# audio_router.net
KiCad netlist of a schematic drawn in EAGLE
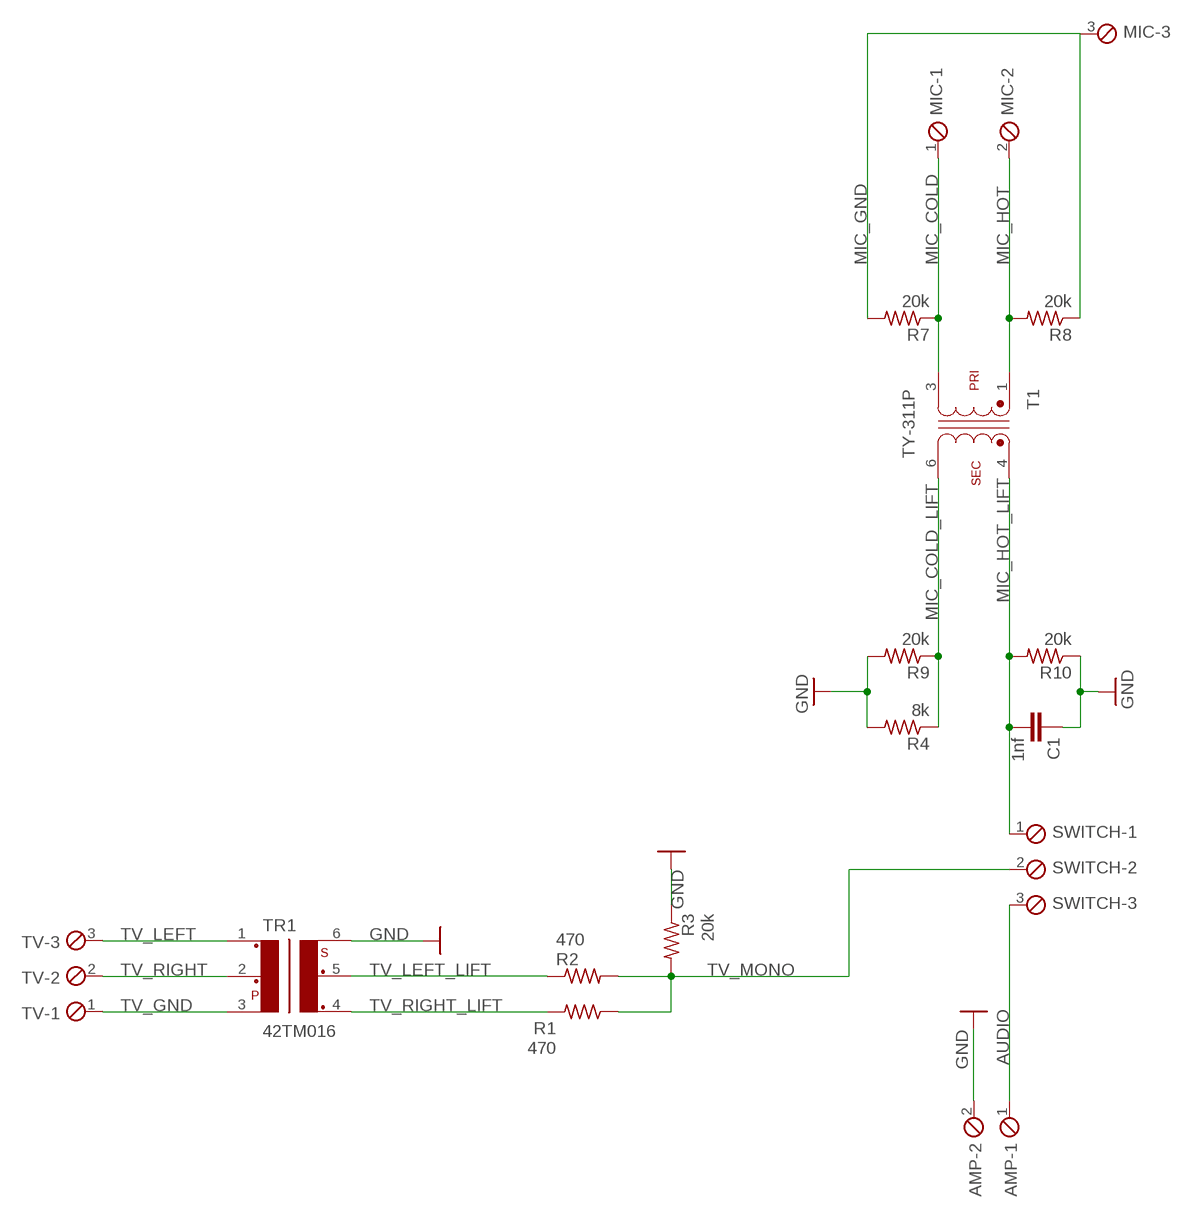
[diagram p0: schematic, sheet 1]

(export (version "E")
  (design (tool "Eeschema 10.0.6"))
  (components
    (comp (ref "AMP")
      (value "TB3POL")
      (footprint "eagle-import:2POL381")
      (libsource (lib "eagle-import") (part "MKDS1/2-3,81"))
    )
    (comp (ref "C1")
      (value "1nf")
      (footprint "eagle-import:CAP-PTH-SMALL-KIT")
      (libsource (lib "eagle-import") (part "0.1UF-KIT-EZ-50V-20%"))
    )
    (comp (ref "MIC")
      (value "TB3POL")
      (footprint "eagle-import:3POL381")
      (libsource (lib "eagle-import") (part "MKDS1/3-3,81"))
    )
    (comp (ref "R1")
      (value "470")
      (footprint "eagle-import:0204_7")
      (libsource (lib "eagle-import") (part "R-US_0204/7"))
    )
    (comp (ref "R2")
      (value "470")
      (footprint "eagle-import:0204_7")
      (libsource (lib "eagle-import") (part "R-US_0204/7"))
    )
    (comp (ref "R3")
      (value "20k")
      (footprint "eagle-import:0204_7")
      (libsource (lib "eagle-import") (part "R-US_0204/7"))
    )
    (comp (ref "R4")
      (value "8k")
      (footprint "eagle-import:0204_7")
      (libsource (lib "eagle-import") (part "R-US_0204/7"))
    )
    (comp (ref "R7")
      (value "20k")
      (footprint "eagle-import:0204_7")
      (libsource (lib "eagle-import") (part "R-US_0204/7"))
    )
    (comp (ref "R8")
      (value "20k")
      (footprint "eagle-import:0204_7")
      (libsource (lib "eagle-import") (part "R-US_0204/7"))
    )
    (comp (ref "R9")
      (value "20k")
      (footprint "eagle-import:0204_7")
      (libsource (lib "eagle-import") (part "R-US_0204/7"))
    )
    (comp (ref "R10")
      (value "20k")
      (footprint "eagle-import:0204_7")
      (libsource (lib "eagle-import") (part "R-US_0204/7"))
    )
    (comp (ref "SWITCH")
      (value "TB3POL")
      (footprint "eagle-import:3POL381")
      (libsource (lib "eagle-import") (part "MKDS1/3-3,81"))
    )
    (comp (ref "T1")
      (value "TY-311P")
      (footprint "eagle-import:XFMR_TY-311P")
      (fields (field (name "MF") "Triad Magnetics"))
      (libsource (lib "eagle-import") (part "TY-311P"))
    )
    (comp (ref "TR1")
      (value "42TM016")
      (footprint "eagle-import:42TM")
      (libsource (lib "eagle-import") (part "42T?M016"))
    )
    (comp (ref "TV")
      (value "TB3POL")
      (footprint "eagle-import:3POL381")
      (libsource (lib "eagle-import") (part "MKDS1/3-3,81"))
    )
  )
  (nets
    (net (code "1") (name "/AUDIO") (class "Default")
      (node (ref "AMP") (pin "1") (pinfunction "1_1") (pintype "passive"))
      (node (ref "SWITCH") (pin "3") (pinfunction "1_3") (pintype "passive"))
    )
    (net (code "2") (name "/MIC_COLD") (class "Default")
      (node (ref "MIC") (pin "1") (pinfunction "1_1") (pintype "passive"))
      (node (ref "R7") (pin "1") (pinfunction "1_1") (pintype "passive"))
      (node (ref "T1") (pin "3") (pinfunction "3_3") (pintype "passive"))
    )
    (net (code "3") (name "/MIC_COLD_LIFT") (class "Default")
      (node (ref "R4") (pin "1") (pinfunction "1_1") (pintype "passive"))
      (node (ref "R9") (pin "1") (pinfunction "1_1") (pintype "passive"))
      (node (ref "T1") (pin "6") (pinfunction "6_6") (pintype "passive"))
    )
    (net (code "4") (name "/MIC_GND") (class "Default")
      (node (ref "MIC") (pin "3") (pinfunction "1_3") (pintype "passive"))
      (node (ref "R7") (pin "2") (pinfunction "2_2") (pintype "passive"))
      (node (ref "R8") (pin "1") (pinfunction "1_1") (pintype "passive"))
    )
    (net (code "5") (name "/MIC_HOT") (class "Default")
      (node (ref "MIC") (pin "2") (pinfunction "1_2") (pintype "passive"))
      (node (ref "R8") (pin "2") (pinfunction "2_2") (pintype "passive"))
      (node (ref "T1") (pin "1") (pinfunction "1_1") (pintype "passive"))
    )
    (net (code "6") (name "/MIC_HOT_LIFT") (class "Default")
      (node (ref "C1") (pin "2") (pinfunction "2_2") (pintype "passive"))
      (node (ref "R10") (pin "2") (pinfunction "2_2") (pintype "passive"))
      (node (ref "SWITCH") (pin "1") (pinfunction "1_1") (pintype "passive"))
      (node (ref "T1") (pin "4") (pinfunction "4_4") (pintype "passive"))
    )
    (net (code "7") (name "/TV_GND") (class "Default")
      (node (ref "TR1") (pin "3") (pinfunction "3_3") (pintype "passive"))
      (node (ref "TV") (pin "1") (pinfunction "1_1") (pintype "passive"))
    )
    (net (code "8") (name "/TV_LEFT") (class "Default")
      (node (ref "TR1") (pin "1") (pinfunction "1_1") (pintype "passive"))
      (node (ref "TV") (pin "3") (pinfunction "1_3") (pintype "passive"))
    )
    (net (code "9") (name "/TV_LEFT_LIFT") (class "Default")
      (node (ref "R2") (pin "1") (pinfunction "1_1") (pintype "passive"))
      (node (ref "TR1") (pin "5") (pinfunction "5_5") (pintype "passive"))
    )
    (net (code "10") (name "/TV_MONO") (class "Default")
      (node (ref "R1") (pin "1") (pinfunction "1_1") (pintype "passive"))
      (node (ref "R2") (pin "2") (pinfunction "2_2") (pintype "passive"))
      (node (ref "R3") (pin "2") (pinfunction "2_2") (pintype "passive"))
      (node (ref "SWITCH") (pin "2") (pinfunction "1_2") (pintype "passive"))
    )
    (net (code "11") (name "/TV_RIGHT") (class "Default")
      (node (ref "TR1") (pin "2") (pinfunction "2_2") (pintype "passive"))
      (node (ref "TV") (pin "2") (pinfunction "1_2") (pintype "passive"))
    )
    (net (code "12") (name "/TV_RIGHT_LIFT") (class "Default")
      (node (ref "R1") (pin "2") (pinfunction "2_2") (pintype "passive"))
      (node (ref "TR1") (pin "4") (pinfunction "4_4") (pintype "passive"))
    )
    (net (code "13") (name "GND") (class "Default")
      (node (ref "AMP") (pin "2") (pinfunction "1_2") (pintype "passive"))
      (node (ref "C1") (pin "1") (pinfunction "1_1") (pintype "passive"))
      (node (ref "R10") (pin "1") (pinfunction "1_1") (pintype "passive"))
      (node (ref "R3") (pin "1") (pinfunction "1_1") (pintype "passive"))
      (node (ref "R4") (pin "2") (pinfunction "2_2") (pintype "passive"))
      (node (ref "R9") (pin "2") (pinfunction "2_2") (pintype "passive"))
      (node (ref "TR1") (pin "6") (pinfunction "6_6") (pintype "passive"))
    )
  )
)
